# eMMC.net
KiCad netlist of a schematic drawn in Altium Designer
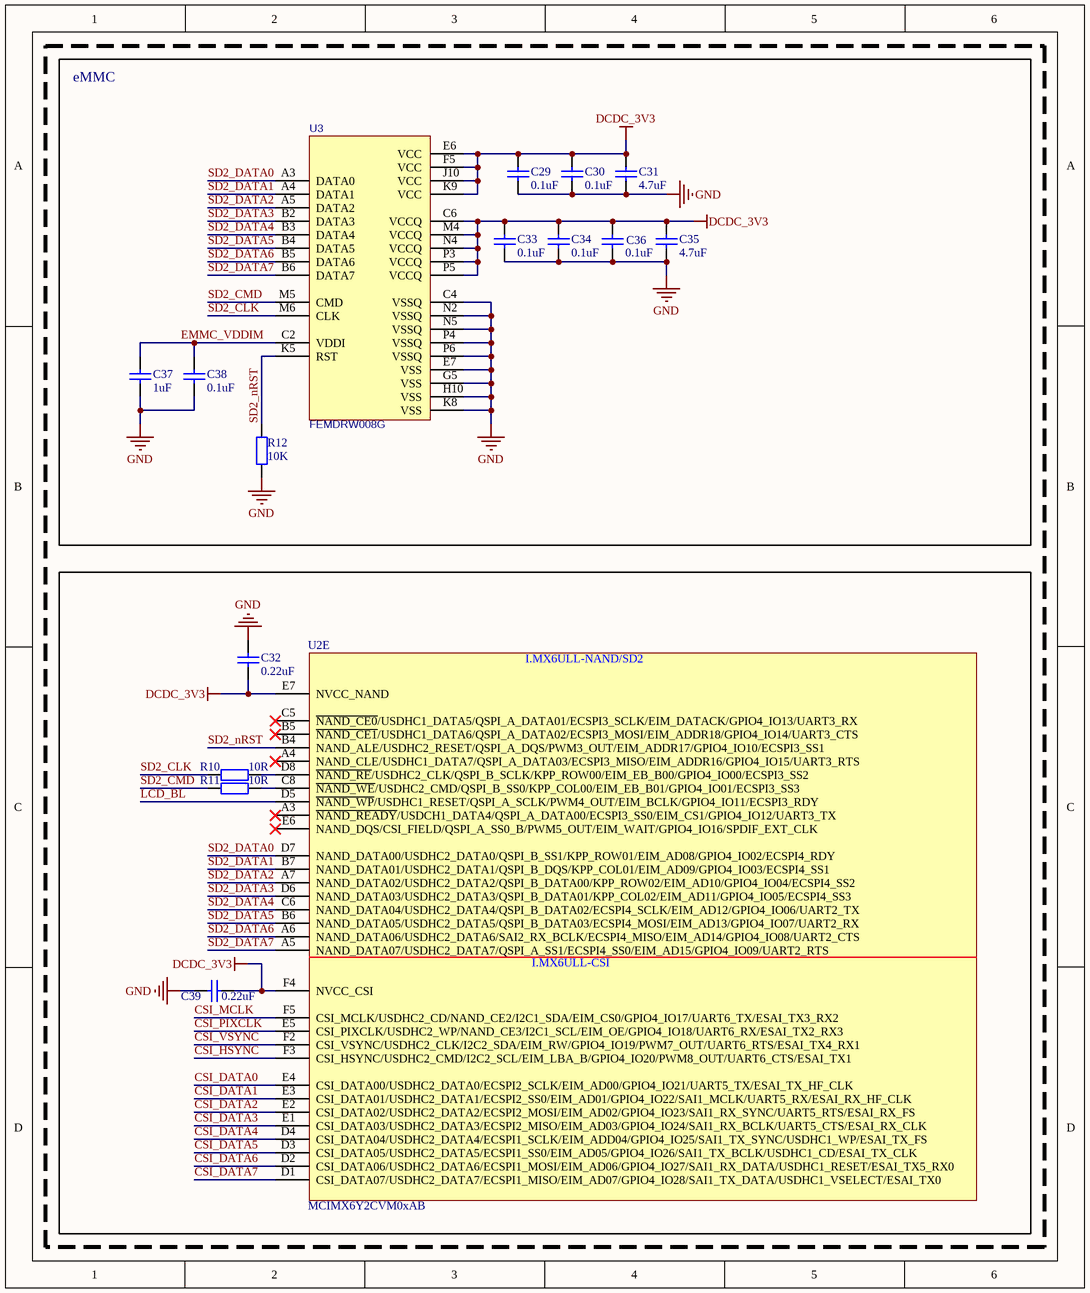
[diagram p0: eMMC.SchDoc]

(export (version "E")
  (design (tool "Eeschema 10.0.6"))
  (components
    (comp (ref "C29")
      (value "0.1uF")
      (footprint "0402_C")
      (description "贴片电容")
      (libsource (lib "My_Devices") (part "0402_C"))
    )
    (comp (ref "C30")
      (value "0.1uF")
      (footprint "0402_C")
      (description "贴片电容")
      (libsource (lib "My_Devices") (part "0402_C"))
    )
    (comp (ref "C31")
      (value "4.7uF")
      (footprint "0402_C")
      (description "贴片电容")
      (libsource (lib "My_Devices") (part "0402_C"))
    )
    (comp (ref "C32")
      (value "0.22uF")
      (footprint "0402_C")
      (description "贴片电容")
      (libsource (lib "My_Devices") (part "0402_C"))
    )
    (comp (ref "C33")
      (value "0.1uF")
      (footprint "0402_C")
      (description "贴片电容")
      (libsource (lib "My_Devices") (part "0402_C"))
    )
    (comp (ref "C34")
      (value "0.1uF")
      (footprint "0402_C")
      (description "贴片电容")
      (libsource (lib "My_Devices") (part "0402_C"))
    )
    (comp (ref "C35")
      (value "4.7uF")
      (footprint "0402_C")
      (description "贴片电容")
      (libsource (lib "My_Devices") (part "0402_C"))
    )
    (comp (ref "C36")
      (value "0.1uF")
      (footprint "0402_C")
      (description "贴片电容")
      (libsource (lib "My_Devices") (part "0402_C"))
    )
    (comp (ref "C37")
      (value "1uF")
      (footprint "0402_C")
      (description "贴片电容")
      (libsource (lib "My_Devices") (part "0402_C"))
    )
    (comp (ref "C38")
      (value "0.1uF")
      (footprint "0402_C")
      (description "贴片电容")
      (libsource (lib "My_Devices") (part "0402_C"))
    )
    (comp (ref "C39")
      (value "0.22uF")
      (footprint "0402_C")
      (description "贴片电容")
      (libsource (lib "My_Devices") (part "0402_C"))
    )
    (comp (ref "R10")
      (value "10R")
      (footprint "0402_R")
      (description "贴片电阻")
      (libsource (lib "My_Devices") (part "0402_R"))
    )
    (comp (ref "R11")
      (value "10R")
      (footprint "0402_R")
      (description "贴片电阻")
      (libsource (lib "My_Devices") (part "0402_R"))
    )
    (comp (ref "R12")
      (value "10K")
      (footprint "0402_R")
      (description "贴片电阻")
      (libsource (lib "") (part "0402_R_1"))
    )
    (comp (ref "U2")
      (value "MCIMX6Y2CVM0xAB")
      (footprint "BGA289_17x17_0.8Pitch")
      (libsource (lib "Linux_Core") (part "MCIMX6Y2CVM0xAB"))
    )
    (comp (ref "U3")
      (value "FEMDRW008G")
      (footprint "BGA169  EMMC")
      (fields
        (field (name "BOM_SUPPLIER PART") "C499918")
        (field (name "BOM_MANUFACTURER PART") "KLM8G1GETF-B041")
        (field (name "CONTRIBUTOR") "LCSC")
      )
      (libsource (lib "Linux_Core") (part "FEMDRW008G"))
    )
  )
  (nets
    (net (code "1") (name "/CSI_DATA0") (class "Default")
      (node (ref "U2") (pin "E4") (pinfunction "CSI_DATA00/USDHC2_DATA0/ECSPI2_SCLK/EIM_AD00/GPIO4_IO21/UART5_TX/ESAI_TX_HF_CLK_E4") (pintype "passive"))
    )
    (net (code "2") (name "/CSI_DATA1") (class "Default")
      (node (ref "U2") (pin "E3") (pinfunction "CSI_DATA01/USDHC2_DATA1/ECSPI2_SS0/EIM_AD01/GPIO4_IO22/SAI1_MCLK/UART5_RX/ESAI_RX_HF_CLK_E3") (pintype "passive"))
    )
    (net (code "3") (name "/CSI_DATA2") (class "Default")
      (node (ref "U2") (pin "E2") (pinfunction "CSI_DATA02/USDHC2_DATA2/ECSPI2_MOSI/EIM_AD02/GPIO4_IO23/SAI1_RX_SYNC/UART5_RTS/ESAI_RX_FS_E2") (pintype "passive"))
    )
    (net (code "4") (name "/CSI_DATA3") (class "Default")
      (node (ref "U2") (pin "E1") (pinfunction "CSI_DATA03/USDHC2_DATA3/ECSPI2_MISO/EIM_AD03/GPIO4_IO24/SAI1_RX_BCLK/UART5_CTS/ESAI_RX_CLK_E1") (pintype "passive"))
    )
    (net (code "5") (name "/CSI_DATA4") (class "Default")
      (node (ref "U2") (pin "D4") (pinfunction "CSI_DATA04/USDHC2_DATA4/ECSPI1_SCLK/EIM_ADD04/GPIO4_IO25/SAI1_TX_SYNC/USDHC1_WP/ESAI_TX_FS_D4") (pintype "passive"))
    )
    (net (code "6") (name "/CSI_DATA5") (class "Default")
      (node (ref "U2") (pin "D3") (pinfunction "CSI_DATA05/USDHC2_DATA5/ECSPI1_SS0/EIM_AD05/GPIO4_IO26/SAI1_TX_BCLK/USDHC1_CD/ESAI_TX_CLK_D3") (pintype "passive"))
    )
    (net (code "7") (name "/CSI_DATA6") (class "Default")
      (node (ref "U2") (pin "D2") (pinfunction "CSI_DATA06/USDHC2_DATA6/ECSPI1_MOSI/EIM_AD06/GPIO4_IO27/SAI1_RX_DATA/USDHC1_RESET/ESAI_TX5_RX0_D2") (pintype "passive"))
    )
    (net (code "8") (name "/CSI_DATA7") (class "Default")
      (node (ref "U2") (pin "D1") (pinfunction "CSI_DATA07/USDHC2_DATA7/ECSPI1_MISO/EIM_AD07/GPIO4_IO28/SAI1_TX_DATA/USDHC1_VSELECT/ESAI_TX0_D1") (pintype "passive"))
    )
    (net (code "9") (name "/CSI_HSYNC") (class "Default")
      (node (ref "U2") (pin "F3") (pinfunction "CSI_HSYNC/USDHC2_CMD/I2C2_SCL/EIM_LBA_B/GPIO4_IO20/PWM8_OUT/UART6_CTS/ESAI_TX1_F3") (pintype "passive"))
    )
    (net (code "10") (name "/CSI_MCLK") (class "Default")
      (node (ref "U2") (pin "F5") (pinfunction "CSI_MCLK/USDHC2_CD/NAND_CE2/I2C1_SDA/EIM_CS0/GPIO4_IO17/UART6_TX/ESAI_TX3_RX2_F5") (pintype "passive"))
    )
    (net (code "11") (name "/CSI_PIXCLK") (class "Default")
      (node (ref "U2") (pin "E5") (pinfunction "CSI_PIXCLK/USDHC2_WP/NAND_CE3/I2C1_SCL/EIM_OE/GPIO4_IO18/UART6_RX/ESAI_TX2_RX3_E5") (pintype "passive"))
    )
    (net (code "12") (name "/CSI_VSYNC") (class "Default")
      (node (ref "U2") (pin "F2") (pinfunction "CSI_VSYNC/USDHC2_CLK/I2C2_SDA/EIM_RW/GPIO4_IO19/PWM7_OUT/UART6_RTS/ESAI_TX4_RX1_F2") (pintype "passive"))
    )
    (net (code "13") (name "/EMMC_VDDIM") (class "Default")
      (node (ref "C37") (pin "2") (pinfunction "2_2") (pintype "passive"))
      (node (ref "C38") (pin "2") (pinfunction "2_2") (pintype "passive"))
      (node (ref "U3") (pin "C2") (pinfunction "VDDI_C2") (pintype "passive"))
    )
    (net (code "14") (name "/LCD_BL") (class "Default")
      (node (ref "U2") (pin "D5") (pinfunction "~{NAND_WP}/USDHC1_RESET/QSPI_A_SCLK/PWM4_OUT/EIM_BCLK/GPIO4_IO11/ECSPI3_RDY_D5") (pintype "passive"))
    )
    (net (code "15") (name "/SD2_CLK") (class "Default")
      (node (ref "R10") (pin "1") (pinfunction "1_1") (pintype "passive"))
      (node (ref "U3") (pin "M6") (pinfunction "CLK_M6") (pintype "passive"))
    )
    (net (code "16") (name "/SD2_CMD") (class "Default")
      (node (ref "R11") (pin "1") (pinfunction "1_1") (pintype "passive"))
      (node (ref "U3") (pin "M5") (pinfunction "CMD_M5") (pintype "passive"))
    )
    (net (code "17") (name "/SD2_DATA0") (class "Default")
      (node (ref "U2") (pin "D7") (pinfunction "NAND_DATA00/USDHC2_DATA0/QSPI_B_SS1/KPP_ROW01/EIM_AD08/GPIO4_IO02/ECSPI4_RDY_D7") (pintype "passive"))
      (node (ref "U3") (pin "A3") (pinfunction "DATA0_A3") (pintype "passive"))
    )
    (net (code "18") (name "/SD2_DATA1") (class "Default")
      (node (ref "U2") (pin "B7") (pinfunction "NAND_DATA01/USDHC2_DATA1/QSPI_B_DQS/KPP_COL01/EIM_AD09/GPIO4_IO03/ECSPI4_SS1_B7") (pintype "passive"))
      (node (ref "U3") (pin "A4") (pinfunction "DATA1_A4") (pintype "passive"))
    )
    (net (code "19") (name "/SD2_DATA2") (class "Default")
      (node (ref "U2") (pin "A7") (pinfunction "NAND_DATA02/USDHC2_DATA2/QSPI_B_DATA00/KPP_ROW02/EIM_AD10/GPIO4_IO04/ECSPI4_SS2_A7") (pintype "passive"))
      (node (ref "U3") (pin "A5") (pinfunction "DATA2_A5") (pintype "passive"))
    )
    (net (code "20") (name "/SD2_DATA3") (class "Default")
      (node (ref "U2") (pin "D6") (pinfunction "NAND_DATA03/USDHC2_DATA3/QSPI_B_DATA01/KPP_COL02/EIM_AD11/GPIO4_IO05/ECSPI4_SS3_D6") (pintype "passive"))
      (node (ref "U3") (pin "B2") (pinfunction "DATA3_B2") (pintype "passive"))
    )
    (net (code "21") (name "/SD2_DATA4") (class "Default")
      (node (ref "U2") (pin "C6") (pinfunction "NAND_DATA04/USDHC2_DATA4/QSPI_B_DATA02/ECSPI4_SCLK/EIM_AD12/GPIO4_IO06/UART2_TX_C6") (pintype "passive"))
      (node (ref "U3") (pin "B3") (pinfunction "DATA4_B3") (pintype "passive"))
    )
    (net (code "22") (name "/SD2_DATA5") (class "Default")
      (node (ref "U2") (pin "B6") (pinfunction "NAND_DATA05/USDHC2_DATA5/QSPI_B_DATA03/ECSPI4_MOSI/EIM_AD13/GPIO4_IO07/UART2_RX_B6") (pintype "passive"))
      (node (ref "U3") (pin "B4") (pinfunction "DATA5_B4") (pintype "passive"))
    )
    (net (code "23") (name "/SD2_DATA6") (class "Default")
      (node (ref "U2") (pin "A6") (pinfunction "NAND_DATA06/USDHC2_DATA6/SAI2_RX_BCLK/ECSPI4_MISO/EIM_AD14/GPIO4_IO08/UART2_CTS_A6") (pintype "passive"))
      (node (ref "U3") (pin "B5") (pinfunction "DATA6_B5") (pintype "passive"))
    )
    (net (code "24") (name "/SD2_DATA7") (class "Default")
      (node (ref "U2") (pin "A5") (pinfunction "NAND_DATA07/USDHC2_DATA7/QSPI_A_SS1/ECSPI4_SS0/EIM_AD15/GPIO4_IO09/UART2_RTS_A5") (pintype "passive"))
      (node (ref "U3") (pin "B6") (pinfunction "DATA7_B6") (pintype "passive"))
    )
    (net (code "25") (name "/SD2_nRST") (class "Default")
      (node (ref "R12") (pin "2") (pinfunction "2_2") (pintype "passive"))
      (node (ref "U2") (pin "B4") (pinfunction "NAND_ALE/USDHC2_RESET/QSPI_A_DQS/PWM3_OUT/EIM_ADDR17/GPIO4_IO10/ECSPI3_SS1_B4") (pintype "passive"))
      (node (ref "U3") (pin "K5") (pinfunction "RST_K5") (pintype "passive"))
    )
    (net (code "26") (name "DCDC_3V3") (class "Default")
      (node (ref "C29") (pin "2") (pinfunction "2_2") (pintype "passive"))
      (node (ref "C30") (pin "2") (pinfunction "2_2") (pintype "passive"))
      (node (ref "C31") (pin "2") (pinfunction "2_2") (pintype "passive"))
      (node (ref "C32") (pin "1") (pinfunction "1_1") (pintype "passive"))
      (node (ref "C33") (pin "2") (pinfunction "2_2") (pintype "passive"))
      (node (ref "C34") (pin "2") (pinfunction "2_2") (pintype "passive"))
      (node (ref "C35") (pin "2") (pinfunction "2_2") (pintype "passive"))
      (node (ref "C36") (pin "2") (pinfunction "2_2") (pintype "passive"))
      (node (ref "C39") (pin "1") (pinfunction "1_1") (pintype "passive"))
      (node (ref "U2") (pin "E7") (pinfunction "NVCC_NAND_E7") (pintype "passive"))
      (node (ref "U2") (pin "F4") (pinfunction "NVCC_CSI_F4") (pintype "passive"))
      (node (ref "U3") (pin "C6") (pinfunction "VCCQ_C6") (pintype "passive"))
      (node (ref "U3") (pin "E6") (pinfunction "VCC_E6") (pintype "passive"))
      (node (ref "U3") (pin "F5") (pinfunction "VCC_F5") (pintype "passive"))
      (node (ref "U3") (pin "J10") (pinfunction "VCC_J10") (pintype "passive"))
      (node (ref "U3") (pin "K9") (pinfunction "VCC_K9") (pintype "passive"))
      (node (ref "U3") (pin "M4") (pinfunction "VCCQ_M4") (pintype "passive"))
      (node (ref "U3") (pin "N4") (pinfunction "VCCQ_N4") (pintype "passive"))
      (node (ref "U3") (pin "P3") (pinfunction "VCCQ_P3") (pintype "passive"))
      (node (ref "U3") (pin "P5") (pinfunction "VCCQ_P5") (pintype "passive"))
    )
    (net (code "27") (name "GND") (class "Default")
      (node (ref "C29") (pin "1") (pinfunction "1_1") (pintype "passive"))
      (node (ref "C30") (pin "1") (pinfunction "1_1") (pintype "passive"))
      (node (ref "C31") (pin "1") (pinfunction "1_1") (pintype "passive"))
      (node (ref "C32") (pin "2") (pinfunction "2_2") (pintype "passive"))
      (node (ref "C33") (pin "1") (pinfunction "1_1") (pintype "passive"))
      (node (ref "C34") (pin "1") (pinfunction "1_1") (pintype "passive"))
      (node (ref "C35") (pin "1") (pinfunction "1_1") (pintype "passive"))
      (node (ref "C36") (pin "1") (pinfunction "1_1") (pintype "passive"))
      (node (ref "C37") (pin "1") (pinfunction "1_1") (pintype "passive"))
      (node (ref "C38") (pin "1") (pinfunction "1_1") (pintype "passive"))
      (node (ref "C39") (pin "2") (pinfunction "2_2") (pintype "passive"))
      (node (ref "R12") (pin "1") (pinfunction "1_1") (pintype "passive"))
      (node (ref "U3") (pin "C4") (pinfunction "VSSQ_C4") (pintype "passive"))
      (node (ref "U3") (pin "E7") (pinfunction "VSS_E7") (pintype "passive"))
      (node (ref "U3") (pin "G5") (pinfunction "VSS_G5") (pintype "passive"))
      (node (ref "U3") (pin "H10") (pinfunction "VSS_H10") (pintype "passive"))
      (node (ref "U3") (pin "K8") (pinfunction "VSS_K8") (pintype "passive"))
      (node (ref "U3") (pin "N2") (pinfunction "VSSQ_N2") (pintype "passive"))
      (node (ref "U3") (pin "N5") (pinfunction "VSSQ_N5") (pintype "passive"))
      (node (ref "U3") (pin "P4") (pinfunction "VSSQ_P4") (pintype "passive"))
      (node (ref "U3") (pin "P6") (pinfunction "VSSQ_P6") (pintype "passive"))
    )
    (net (code "28") (name "Net-(U2E-~{NAND_RE}{slash}USDHC2_CLK{slash}QSPI_B_SCLK{slash}KPP_ROW00{slash}EIM_EB_B00{slash}GPIO4_IO00{slash}ECSPI3_SS2)") (class "Default")
      (node (ref "R10") (pin "2") (pinfunction "2_2") (pintype "passive"))
      (node (ref "U2") (pin "D8") (pinfunction "~{NAND_RE}/USDHC2_CLK/QSPI_B_SCLK/KPP_ROW00/EIM_EB_B00/GPIO4_IO00/ECSPI3_SS2_D8") (pintype "passive"))
    )
    (net (code "29") (name "Net-(U2E-~{NAND_WE}{slash}USDHC2_CMD{slash}QSPI_B_SS0{slash}KPP_COL00{slash}EIM_EB_B01{slash}GPIO4_IO01{slash}ECSPI3_SS3)") (class "Default")
      (node (ref "R11") (pin "2") (pinfunction "2_2") (pintype "passive"))
      (node (ref "U2") (pin "C8") (pinfunction "~{NAND_WE}/USDHC2_CMD/QSPI_B_SS0/KPP_COL00/EIM_EB_B01/GPIO4_IO01/ECSPI3_SS3_C8") (pintype "passive"))
    )
    (net (code "30") (name "unconnected-(U2E-NAND_CLE{slash}USDHC1_DATA7{slash}QSPI_A_DATA03{slash}ECSPI3_MISO{slash}EIM_ADDR16{slash}GPIO4_IO15{slash}UART3_RTS-PadA4)") (class "Default")
      (node (ref "U2") (pin "A4") (pinfunction "NAND_CLE/USDHC1_DATA7/QSPI_A_DATA03/ECSPI3_MISO/EIM_ADDR16/GPIO4_IO15/UART3_RTS_A4") (pintype "passive+no_connect"))
    )
    (net (code "31") (name "unconnected-(U2E-NAND_DQS{slash}CSI_FIELD{slash}QSPI_A_SS0_B{slash}PWM5_OUT{slash}EIM_WAIT{slash}GPIO4_IO16{slash}SPDIF_EXT_CLK-PadE6)") (class "Default")
      (node (ref "U2") (pin "E6") (pinfunction "NAND_DQS/CSI_FIELD/QSPI_A_SS0_B/PWM5_OUT/EIM_WAIT/GPIO4_IO16/SPDIF_EXT_CLK_E6") (pintype "passive+no_connect"))
    )
    (net (code "32") (name "unconnected-(U2E-~{NAND_CE0}{slash}USDHC1_DATA5{slash}QSPI_A_DATA01{slash}ECSPI3_SCLK{slash}EIM_DATACK{slash}GPIO4_IO13{slash}UART3_RX-PadC5)") (class "Default")
      (node (ref "U2") (pin "C5") (pinfunction "~{NAND_CE0}/USDHC1_DATA5/QSPI_A_DATA01/ECSPI3_SCLK/EIM_DATACK/GPIO4_IO13/UART3_RX_C5") (pintype "passive+no_connect"))
    )
    (net (code "33") (name "unconnected-(U2E-~{NAND_CE1}{slash}USDHC1_DATA6{slash}QSPI_A_DATA02{slash}ECSPI3_MOSI{slash}EIM_ADDR18{slash}GPIO4_IO14{slash}UART3_CTS-PadB5)") (class "Default")
      (node (ref "U2") (pin "B5") (pinfunction "~{NAND_CE1}/USDHC1_DATA6/QSPI_A_DATA02/ECSPI3_MOSI/EIM_ADDR18/GPIO4_IO14/UART3_CTS_B5") (pintype "passive+no_connect"))
    )
    (net (code "34") (name "unconnected-(U2E-~{NAND_READY}{slash}USDCH1_DATA4{slash}QSPI_A_DATA00{slash}ECSPI3_SS0{slash}EIM_CS1{slash}GPIO4_IO12{slash}UART3_TX-PadA3)") (class "Default")
      (node (ref "U2") (pin "A3") (pinfunction "~{NAND_READY}/USDCH1_DATA4/QSPI_A_DATA00/ECSPI3_SS0/EIM_CS1/GPIO4_IO12/UART3_TX_A3") (pintype "passive+no_connect"))
    )
  )
)
